# SCH_Induction-DC-motor_2025-01-21.net
KiCad netlist of a schematic drawn in EasyEDA
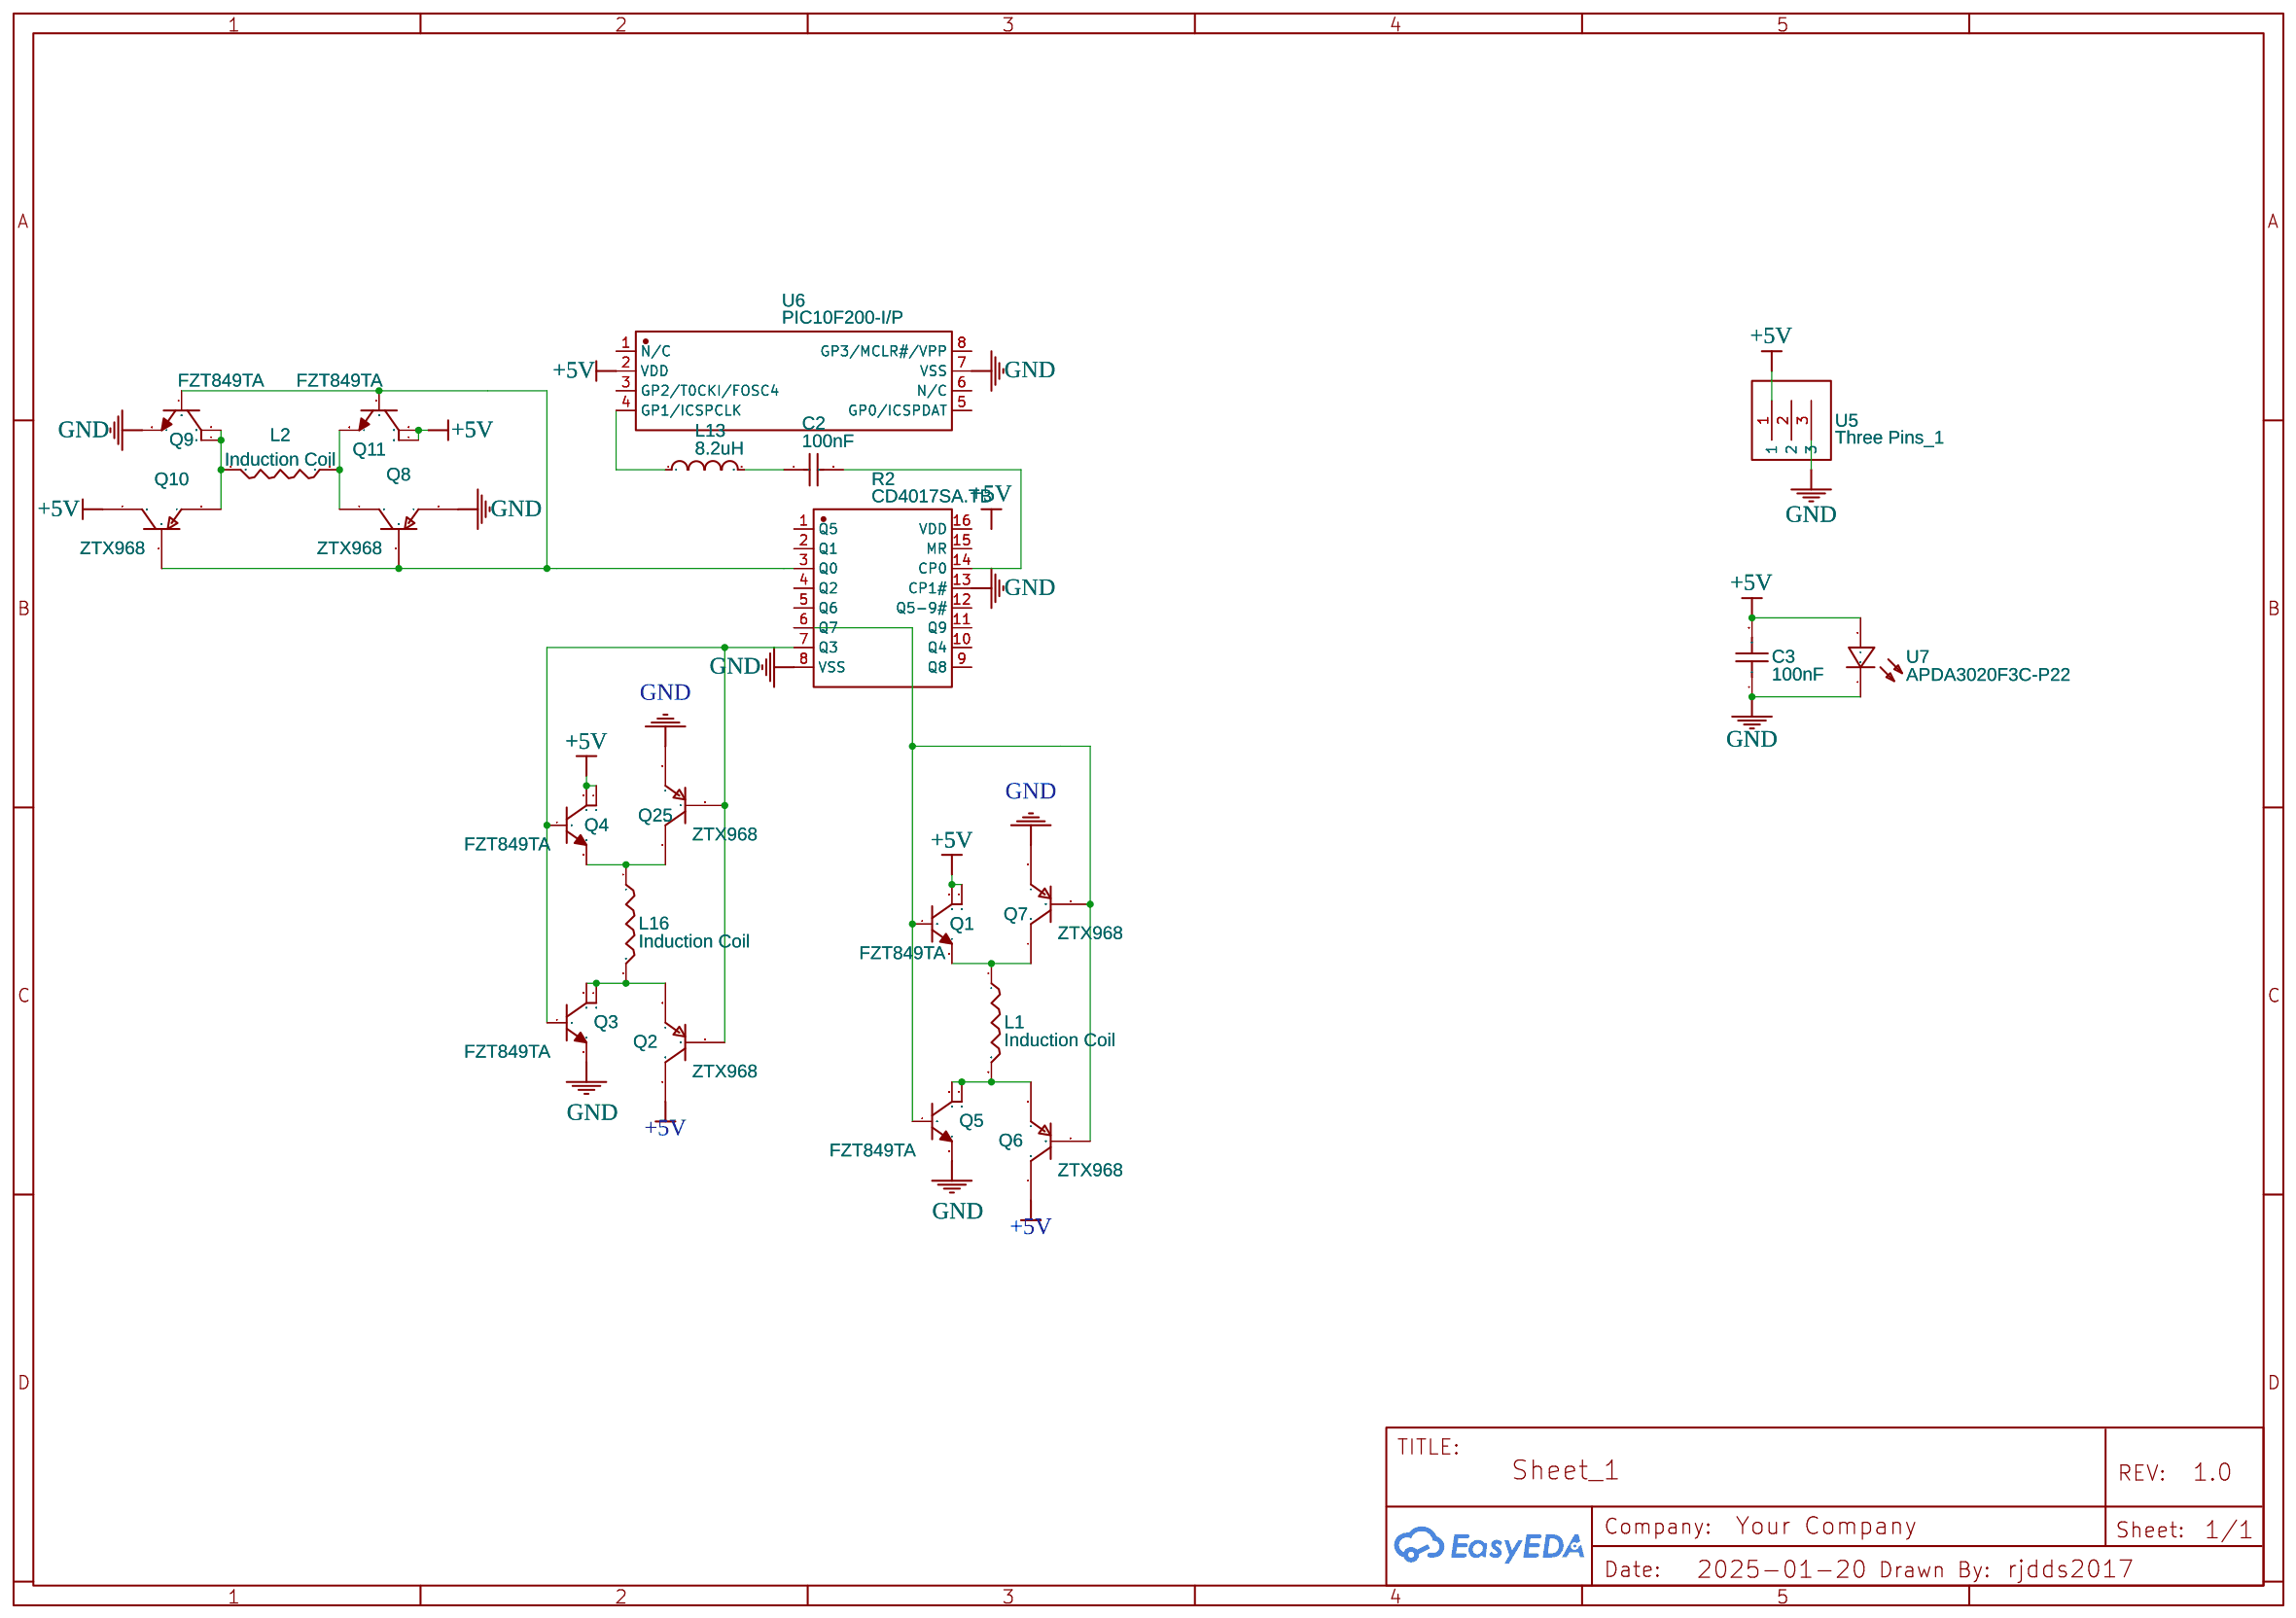
[diagram p0: schematic sheet]

(export (version "E")
  (design (tool "Eeschema 10.0.6"))
  (components
    (comp (ref "C2")
      (value "100nF")
      (fields
        (field (name "Manufacturer Part") "Calibration capacitor100nF（104）100V,5%")
        (field (name "Manufacturer") "ReliaPro")
      )
      (libsource (lib "") (part "Calibration capacitor100nF（104）100V,5%"))
    )
    (comp (ref "C3")
      (value "100nF")
      (fields
        (field (name "Manufacturer Part") "GRM188R72A104KA35D")
        (field (name "Manufacturer") "muRata(村田)")
      )
      (libsource (lib "") (part "GRM188R72A104KA35D"))
    )
    (comp (ref "L1") (value "Induction Coil") (libsource (lib "") (part "Induction Coil_1")))
    (comp (ref "L2") (value "Induction Coil") (libsource (lib "") (part "Induction Coil")))
    (comp (ref "L13")
      (value "8.2uH")
      (fields (field (name "Manufacturer Part") "SMRH5D28-8R2NT") (field (name "Manufacturer") "SXN(顺翔诺)"))
      (libsource (lib "") (part "Power inductorSMRH5D28-8R2NT"))
    )
    (comp (ref "L16") (value "Induction Coil") (libsource (lib "") (part "Induction Coil_1")))
    (comp (ref "Q1") (value "ZTX968") (libsource (lib "") (part "ZTX968")))
    (comp (ref "Q2") (value "ZTX968") (libsource (lib "") (part "ZTX968")))
    (comp (ref "Q3")
      (value "FZT849TA")
      (fields (field (name "Manufacturer") "DIODES(美台)"))
      (libsource (lib "") (part "FZT849TA_1"))
    )
    (comp (ref "Q4") (value "ZTX968") (libsource (lib "") (part "ZTX968")))
    (comp (ref "Q5")
      (value "FZT849TA")
      (fields (field (name "Manufacturer") "DIODES(美台)"))
      (libsource (lib "") (part "FZT849TA_1"))
    )
    (comp (ref "Q6") (value "ZTX968") (libsource (lib "") (part "ZTX968")))
    (comp (ref "Q7")
      (value "FZT849TA")
      (fields (field (name "Manufacturer") "DIODES(美台)"))
      (libsource (lib "") (part "FZT849TA_1"))
    )
    (comp (ref "Q8") (value "ZTX968") (libsource (lib "") (part "ZTX968_1")))
    (comp (ref "Q9")
      (value "FZT849TA")
      (fields (field (name "Manufacturer") "DIODES(美台)"))
      (libsource (lib "") (part "FZT849TA"))
    )
    (comp (ref "Q10") (value "ZTX968") (libsource (lib "") (part "ZTX968_1")))
    (comp (ref "Q11")
      (value "FZT849TA")
      (fields (field (name "Manufacturer") "DIODES(美台)"))
      (libsource (lib "") (part "FZT849TA"))
    )
    (comp (ref "Q25")
      (value "FZT849TA")
      (fields (field (name "Manufacturer") "DIODES(美台)"))
      (libsource (lib "") (part "FZT849TA_1"))
    )
    (comp (ref "R2")
      (value "CD4017SA.TB")
      (fields (field (name "Manufacturer") "I-CORE(中微爱芯)"))
      (libsource (lib "") (part "CD4017SA.TB"))
    )
    (comp (ref "U5") (value "Three Pins_1") (libsource (lib "") (part "Three Pins_1")))
    (comp (ref "U6")
      (value "PIC10F200-I/P")
      (fields (field (name "Manufacturer") "MICROCHIP(美国微芯)"))
      (libsource (lib "") (part "PIC10F200-I/P"))
    )
    (comp (ref "U7")
      (value "APDA3020F3C-P22")
      (fields (field (name "Manufacturer") "Kingbright"))
      (libsource (lib "") (part "APDA3020F3C-P22"))
    )
  )
  (nets
    (net (code "1") (name "+5V") (class "Default")
      (node (ref "C3") (pin "2") (pinfunction "2_2") (pintype "unspecified"))
      (node (ref "Q10") (pin "1") (pinfunction "C_1") (pintype "unspecified"))
      (node (ref "Q11") (pin "2") (pinfunction "C_2") (pintype "unspecified"))
      (node (ref "Q11") (pin "4") (pinfunction "C_4") (pintype "unspecified"))
      (node (ref "Q2") (pin "1") (pinfunction "C_1") (pintype "unspecified"))
      (node (ref "Q25") (pin "2") (pinfunction "C_2") (pintype "unspecified"))
      (node (ref "Q25") (pin "4") (pinfunction "C_4") (pintype "unspecified"))
      (node (ref "Q6") (pin "1") (pinfunction "C_1") (pintype "unspecified"))
      (node (ref "Q7") (pin "2") (pinfunction "C_2") (pintype "unspecified"))
      (node (ref "Q7") (pin "4") (pinfunction "C_4") (pintype "unspecified"))
      (node (ref "U5") (pin "1") (pinfunction "1_1") (pintype "unspecified"))
      (node (ref "U6") (pin "2") (pinfunction "VDD_2") (pintype "unspecified"))
      (node (ref "U7") (pin "2") (pinfunction "A_2") (pintype "unspecified"))
    )
    (net (code "2") (name "GND") (class "Default")
      (node (ref "C3") (pin "1") (pinfunction "1_1") (pintype "unspecified"))
      (node (ref "Q1") (pin "3") (pinfunction "E_3") (pintype "unspecified"))
      (node (ref "Q3") (pin "3") (pinfunction "E_3") (pintype "unspecified"))
      (node (ref "Q4") (pin "3") (pinfunction "E_3") (pintype "unspecified"))
      (node (ref "Q5") (pin "3") (pinfunction "E_3") (pintype "unspecified"))
      (node (ref "Q8") (pin "3") (pinfunction "E_3") (pintype "unspecified"))
      (node (ref "Q9") (pin "3") (pinfunction "E_3") (pintype "unspecified"))
      (node (ref "R2") (pin "13") (pinfunction "CP1#_13") (pintype "unspecified"))
      (node (ref "R2") (pin "8") (pinfunction "VSS_8") (pintype "unspecified"))
      (node (ref "U5") (pin "3") (pinfunction "3_3") (pintype "unspecified"))
      (node (ref "U6") (pin "7") (pinfunction "VSS_7") (pintype "unspecified"))
      (node (ref "U7") (pin "1") (pinfunction "C_1") (pintype "unspecified"))
    )
    (net (code "3") (name "Net-(C2-Pad1)") (class "Default")
      (node (ref "C2") (pin "1") (pinfunction "1_1") (pintype "input"))
      (node (ref "L13") (pin "2") (pinfunction "2_2") (pintype "unspecified"))
    )
    (net (code "4") (name "Net-(Q1-B)") (class "Default")
      (node (ref "Q1") (pin "2") (pinfunction "B_2") (pintype "unspecified"))
      (node (ref "Q5") (pin "1") (pinfunction "B_1") (pintype "unspecified"))
      (node (ref "Q6") (pin "2") (pinfunction "B_2") (pintype "unspecified"))
      (node (ref "Q7") (pin "1") (pinfunction "B_1") (pintype "unspecified"))
      (node (ref "R2") (pin "6") (pinfunction "Q7_6") (pintype "unspecified"))
    )
    (net (code "5") (name "Net-(Q1-C)") (class "Default")
      (node (ref "L1") (pin "1") (pinfunction "1_1") (pintype "unspecified"))
      (node (ref "Q1") (pin "1") (pinfunction "C_1") (pintype "unspecified"))
      (node (ref "Q7") (pin "3") (pinfunction "E_3") (pintype "unspecified"))
    )
    (net (code "6") (name "Net-(Q2-B)") (class "Default")
      (node (ref "Q2") (pin "2") (pinfunction "B_2") (pintype "unspecified"))
      (node (ref "Q25") (pin "1") (pinfunction "B_1") (pintype "unspecified"))
      (node (ref "Q3") (pin "1") (pinfunction "B_1") (pintype "unspecified"))
      (node (ref "Q4") (pin "2") (pinfunction "B_2") (pintype "unspecified"))
      (node (ref "R2") (pin "7") (pinfunction "Q3_7") (pintype "unspecified"))
    )
    (net (code "7") (name "Net-(Q2-E)") (class "Default")
      (node (ref "L16") (pin "2") (pinfunction "2_2") (pintype "unspecified"))
      (node (ref "Q2") (pin "3") (pinfunction "E_3") (pintype "unspecified"))
      (node (ref "Q3") (pin "2") (pinfunction "C_2") (pintype "unspecified"))
      (node (ref "Q3") (pin "4") (pinfunction "C_4") (pintype "unspecified"))
    )
    (net (code "8") (name "Net-(Q6-E)") (class "Default")
      (node (ref "L1") (pin "2") (pinfunction "2_2") (pintype "unspecified"))
      (node (ref "Q5") (pin "2") (pinfunction "C_2") (pintype "unspecified"))
      (node (ref "Q5") (pin "4") (pinfunction "C_4") (pintype "unspecified"))
      (node (ref "Q6") (pin "3") (pinfunction "E_3") (pintype "unspecified"))
    )
    (net (code "9") (name "Net-(Q10-B)") (class "Default")
      (node (ref "Q10") (pin "2") (pinfunction "B_2") (pintype "unspecified"))
      (node (ref "Q11") (pin "1") (pinfunction "B_1") (pintype "unspecified"))
      (node (ref "Q8") (pin "2") (pinfunction "B_2") (pintype "unspecified"))
      (node (ref "Q9") (pin "1") (pinfunction "B_1") (pintype "unspecified"))
      (node (ref "R2") (pin "3") (pinfunction "Q0_3") (pintype "unspecified"))
    )
    (net (code "10") (name "Net-(Q10-E)") (class "Default")
      (node (ref "L2") (pin "2") (pinfunction "2_2") (pintype "unspecified"))
      (node (ref "Q10") (pin "3") (pinfunction "E_3") (pintype "unspecified"))
      (node (ref "Q9") (pin "2") (pinfunction "C_2") (pintype "unspecified"))
      (node (ref "Q9") (pin "4") (pinfunction "C_4") (pintype "unspecified"))
    )
    (net (code "11") (name "Net-(Q11-E)") (class "Default")
      (node (ref "L2") (pin "1") (pinfunction "1_1") (pintype "unspecified"))
      (node (ref "Q11") (pin "3") (pinfunction "E_3") (pintype "unspecified"))
      (node (ref "Q8") (pin "1") (pinfunction "C_1") (pintype "unspecified"))
    )
    (net (code "12") (name "Net-(Q25-E)") (class "Default")
      (node (ref "L16") (pin "1") (pinfunction "1_1") (pintype "unspecified"))
      (node (ref "Q25") (pin "3") (pinfunction "E_3") (pintype "unspecified"))
      (node (ref "Q4") (pin "1") (pinfunction "C_1") (pintype "unspecified"))
    )
    (net (code "13") (name "Net-(R2-CP0)") (class "Default")
      (node (ref "C2") (pin "2") (pinfunction "2_2") (pintype "input"))
      (node (ref "R2") (pin "14") (pinfunction "CP0_14") (pintype "unspecified"))
    )
    (net (code "14") (name "Net-(U6-GP1{slash}ICSPCLK)") (class "Default")
      (node (ref "L13") (pin "1") (pinfunction "1_1") (pintype "unspecified"))
      (node (ref "U6") (pin "4") (pinfunction "GP1/ICSPCLK_4") (pintype "unspecified"))
    )
    (net (code "15") (name "unconnected-(R2-MR-Pad15)") (class "Default")
      (node (ref "R2") (pin "15") (pinfunction "MR_15") (pintype "unspecified"))
    )
    (net (code "16") (name "unconnected-(R2-Q1-Pad2)") (class "Default")
      (node (ref "R2") (pin "2") (pinfunction "Q1_2") (pintype "unspecified"))
    )
    (net (code "17") (name "unconnected-(R2-Q2-Pad4)") (class "Default")
      (node (ref "R2") (pin "4") (pinfunction "Q2_4") (pintype "unspecified"))
    )
    (net (code "18") (name "unconnected-(R2-Q4-Pad10)") (class "Default")
      (node (ref "R2") (pin "10") (pinfunction "Q4_10") (pintype "unspecified"))
    )
    (net (code "19") (name "unconnected-(R2-Q5-9#-Pad12)") (class "Default")
      (node (ref "R2") (pin "12") (pinfunction "Q5-9#_12") (pintype "unspecified"))
    )
    (net (code "20") (name "unconnected-(R2-Q5-Pad1)") (class "Default")
      (node (ref "R2") (pin "1") (pinfunction "Q5_1") (pintype "unspecified"))
    )
    (net (code "21") (name "unconnected-(R2-Q6-Pad5)") (class "Default")
      (node (ref "R2") (pin "5") (pinfunction "Q6_5") (pintype "unspecified"))
    )
    (net (code "22") (name "unconnected-(R2-Q8-Pad9)") (class "Default")
      (node (ref "R2") (pin "9") (pinfunction "Q8_9") (pintype "unspecified"))
    )
    (net (code "23") (name "unconnected-(R2-Q9-Pad11)") (class "Default")
      (node (ref "R2") (pin "11") (pinfunction "Q9_11") (pintype "unspecified"))
    )
    (net (code "24") (name "unconnected-(R2-VDD-Pad16)") (class "Default")
      (node (ref "R2") (pin "16") (pinfunction "VDD_16") (pintype "unspecified"))
    )
    (net (code "25") (name "unconnected-(U5-Pad2)") (class "Default")
      (node (ref "U5") (pin "2") (pinfunction "2_2") (pintype "unspecified"))
    )
    (net (code "26") (name "unconnected-(U6-GP0{slash}ICSPDAT-Pad5)") (class "Default")
      (node (ref "U6") (pin "5") (pinfunction "GP0/ICSPDAT_5") (pintype "unspecified"))
    )
    (net (code "27") (name "unconnected-(U6-GP2{slash}T0CKI{slash}FOSC4-Pad3)") (class "Default")
      (node (ref "U6") (pin "3") (pinfunction "GP2/T0CKI/FOSC4_3") (pintype "unspecified"))
    )
    (net (code "28") (name "unconnected-(U6-GP3{slash}MCLR#{slash}VPP-Pad8)") (class "Default")
      (node (ref "U6") (pin "8") (pinfunction "GP3/MCLR#/VPP_8") (pintype "unspecified"))
    )
    (net (code "29") (name "unconnected-(U6-N{slash}C-Pad1)") (class "Default")
      (node (ref "U6") (pin "1") (pinfunction "N/C_1") (pintype "unspecified"))
    )
    (net (code "30") (name "unconnected-(U6-N{slash}C-Pad6)") (class "Default")
      (node (ref "U6") (pin "6") (pinfunction "N/C_6") (pintype "unspecified"))
    )
  )
)
